# UpperMotor_v1_0_2.net
KiCad netlist of a schematic drawn in EasyEDA Pro
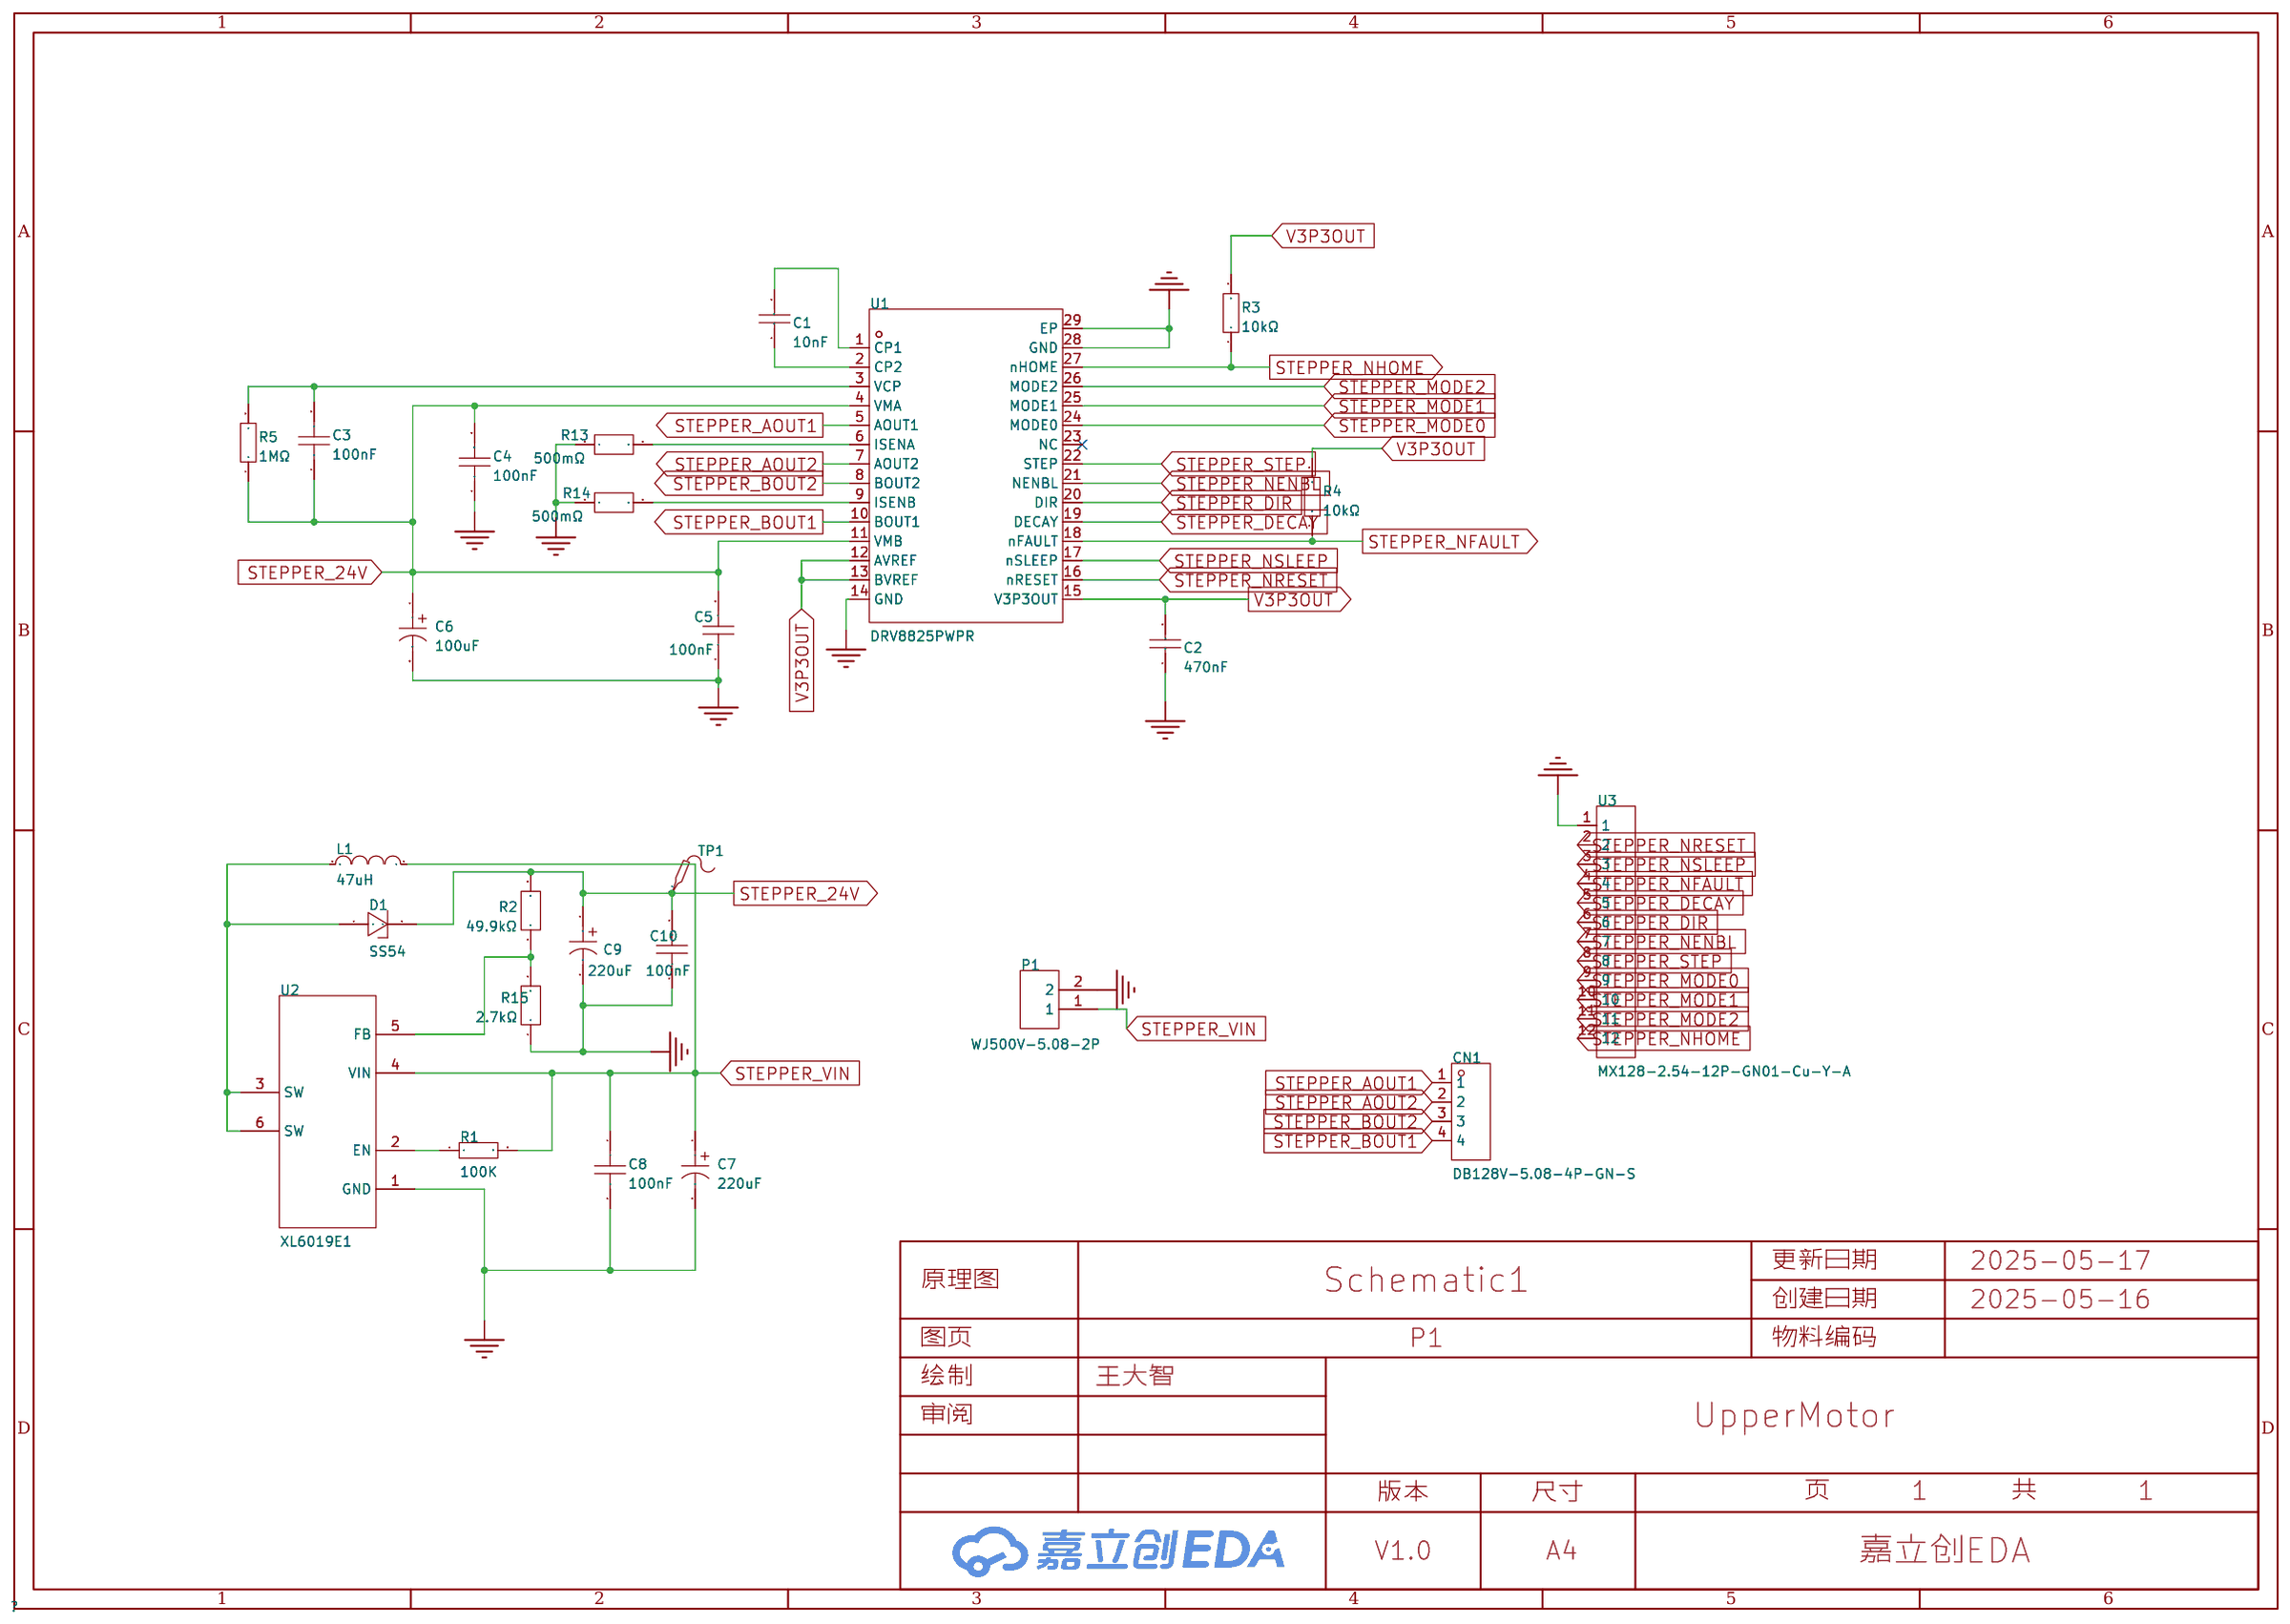
[diagram p0: schematic sheet]

(export (version "E")
  (design (tool "Eeschema 10.0.6"))
  (components
    (comp (ref "C1")
      (value "10nF")
      (footprint "easyedapro:C0603")
      (description "容值:10nF;精度:±10%;额定电压:50V;材质(温度系数):X7R;")
      (fields
        (field (name "Manufacturer Part") "CL10B103KB8NNNC")
        (field (name "Manufacturer") "SAMSUNG(三星)")
      )
      (libsource (lib "easyedapro") (part "CL10B103KB8NNNC"))
    )
    (comp (ref "C2")
      (value "470nF")
      (footprint "easyedapro:C0603")
      (description "容值:470nF;精度:±10%;额定电压:25V;材质(温度系数):X7R;")
      (fields
        (field (name "Manufacturer Part") "CL10B474KA8NNNC")
        (field (name "Manufacturer") "SAMSUNG(三星)")
      )
      (libsource (lib "easyedapro") (part "CL10B474KA8NNNC"))
    )
    (comp (ref "C3")
      (value "100nF")
      (footprint "easyedapro:C0603")
      (description "容值:100nF;精度:±10%;额定电压:50V;温度系数:X7R;")
      (fields
        (field (name "Manufacturer Part") "CGA0603X7R104K500JT")
        (field (name "Manufacturer") "HRE(芯声)")
      )
      (libsource (lib "easyedapro") (part "CGA0603X7R104K500JT"))
    )
    (comp (ref "C4")
      (value "100nF")
      (footprint "easyedapro:C0603")
      (description "容值:100nF;精度:±10%;额定电压:50V;温度系数:X7R;")
      (fields
        (field (name "Manufacturer Part") "CGA0603X7R104K500JT")
        (field (name "Manufacturer") "HRE(芯声)")
      )
      (libsource (lib "easyedapro") (part "CGA0603X7R104K500JT"))
    )
    (comp (ref "C5")
      (value "100nF")
      (footprint "easyedapro:C0603")
      (description "容值:100nF;精度:±10%;额定电压:50V;温度系数:X7R;")
      (fields
        (field (name "Manufacturer Part") "CGA0603X7R104K500JT")
        (field (name "Manufacturer") "HRE(芯声)")
      )
      (libsource (lib "easyedapro") (part "CGA0603X7R104K500JT"))
    )
    (comp (ref "C6")
      (value "100uF")
      (footprint "easyedapro:CAP-SMD_BD8.1-L8.3-W8.3-LS9.3-FD")
      (description "容值:100uF;精度:±20%;额定电压:50V;纹波电流:300mA@100kHz;等效串联电阻:600mΩ@100kHz;")
      (fields
        (field (name "Manufacturer Part") "GVE1H107M0810CNVC")
        (field (name "Manufacturer") "HRK(鸿瑞凯电子)")
      )
      (libsource (lib "easyedapro") (part "GVE1H107M0810CNVC"))
    )
    (comp (ref "C7")
      (value "220uF")
      (footprint "easyedapro:CAP-SMD_BD8.0-L8.3-W8.3-FD")
      (description "容值:220uF;精度:±20%;额定电压:35V;纹波电流:175mA@120Hz;")
      (fields
        (field (name "Manufacturer Part") "GVT1V227M0810CNVC")
        (field (name "Manufacturer") "HRK(鸿瑞凯电子)")
      )
      (libsource (lib "easyedapro") (part "GVT1V227M0810CNVC"))
    )
    (comp (ref "C8")
      (value "100nF")
      (footprint "easyedapro:C0603")
      (libsource (lib "easyedapro") (part "CapAcitance"))
    )
    (comp (ref "C9")
      (value "220uF")
      (footprint "easyedapro:CAP-SMD_BD8.0-L8.3-W8.3-FD")
      (description "容值:220uF;精度:±20%;额定电压:35V;纹波电流:175mA@120Hz;")
      (fields
        (field (name "Manufacturer Part") "GVT1V227M0810CNVC")
        (field (name "Manufacturer") "HRK(鸿瑞凯电子)")
      )
      (libsource (lib "easyedapro") (part "GVT1V227M0810CNVC"))
    )
    (comp (ref "C10")
      (value "100nF")
      (footprint "easyedapro:C0603")
      (libsource (lib "easyedapro") (part "CapAcitance"))
    )
    (comp (ref "CN1")
      (value "DB128V-5.08-4P-GN-S")
      (footprint "easyedapro:CONN-TH_4P-P5.08_DIBO_DB128V-5.08")
      (fields (field (name "Manufacturer") "DORABO(地博电气)"))
      (libsource (lib "easyedapro") (part "DB128V-5.08-4P-GN-S"))
    )
    (comp (ref "D1")
      (value "SS54")
      (footprint "easyedapro:SMA_L4.3-W2.6-LS5.0-FD")
      (description "二极管配置:独立式;正向压降(Vf):550mV@5.0A;直流反向耐压(Vr):40V;整流电流:5A;")
      (fields (field (name "Manufacturer") "宏迦橙"))
      (libsource (lib "easyedapro") (part "SS54_C7420369"))
    )
    (comp (ref "L1")
      (value "47uH")
      (footprint "easyedapro:IND-SMD_L11.5-W10.0_SMMS1040")
      (description "电感值:47uH;精度:±20%;额定电流:3A;饱和电流(Isat):4.5A;类型:一体成型电感;")
      (fields (field (name "Manufacturer Part") "SMMS1040-470M") (field (name "Manufacturer") "SXN(顺翔诺)"))
      (libsource (lib "easyedapro") (part "SMMS1040-470M"))
    )
    (comp (ref "P1")
      (value "WJ500V-5.08-2P")
      (footprint "easyedapro:CONN-TH_2P-P5.00_WJ500V-5.08-2P")
      (fields (field (name "Manufacturer") "KANGNEX(康奈克斯电气)"))
      (libsource (lib "easyedapro") (part "WJ500V-5.08-2P-14-00A"))
    )
    (comp (ref "R1") (value "100K") (footprint "easyedapro:R0603") (libsource (lib "easyedapro") (part "电阻")))
    (comp (ref "R2")
      (value "49.9kΩ")
      (footprint "easyedapro:R0603")
      (description "电阻类型:厚膜电阻;阻值:49.9kΩ;精度:±1%;功率:100mW;最大工作电压:75V;温度系数:±100ppm/°C;")
      (fields (field (name "Manufacturer Part") "FRC0603F4992TS") (field (name "Manufacturer") "FOJAN(富捷)"))
      (libsource (lib "easyedapro") (part "FRC0603F4992TS"))
    )
    (comp (ref "R3")
      (value "10kΩ")
      (footprint "easyedapro:R0603")
      (description "电阻类型:厚膜电阻;阻值:10kΩ;精度:±1%;功率:100mW;最大工作电压:75V;温度系数:±100ppm/°C;")
      (fields (field (name "Manufacturer Part") "RC0603FR-0710KL") (field (name "Manufacturer") "YAGEO(国巨)"))
      (libsource (lib "easyedapro") (part "RC0603FR-0710KL"))
    )
    (comp (ref "R4")
      (value "10kΩ")
      (footprint "easyedapro:R0603")
      (description "电阻类型:厚膜电阻;阻值:10kΩ;精度:±1%;功率:100mW;最大工作电压:75V;温度系数:±100ppm/°C;")
      (fields (field (name "Manufacturer Part") "RC0603FR-0710KL") (field (name "Manufacturer") "YAGEO(国巨)"))
      (libsource (lib "easyedapro") (part "RC0603FR-0710KL"))
    )
    (comp (ref "R5")
      (value "1MΩ")
      (footprint "easyedapro:R0603")
      (fields
        (field (name "Manufacturer Part") "0603WAF1004T5E")
        (field (name "Manufacturer") "UNI-ROYAL(厚声)")
      )
      (libsource (lib "easyedapro") (part "电阻"))
    )
    (comp (ref "R13")
      (value "500mΩ")
      (footprint "easyedapro:R0603")
      (description "电阻类型:厚膜电阻;阻值:500mΩ;精度:±5%;功率:100mW;最大工作电压:100V;温度系数:±300ppm/°C;")
      (fields (field (name "Manufacturer Part") "FRL0603JR500TS") (field (name "Manufacturer") "FOJAN(富捷)"))
      (libsource (lib "easyedapro") (part "FRL0603JR500TS"))
    )
    (comp (ref "R14")
      (value "500mΩ")
      (footprint "easyedapro:R0603")
      (description "电阻类型:厚膜电阻;阻值:500mΩ;精度:±5%;功率:100mW;最大工作电压:100V;温度系数:±300ppm/°C;")
      (fields (field (name "Manufacturer Part") "FRL0603JR500TS") (field (name "Manufacturer") "FOJAN(富捷)"))
      (libsource (lib "easyedapro") (part "FRL0603JR500TS"))
    )
    (comp (ref "R15")
      (value "2.7kΩ")
      (footprint "easyedapro:R0603")
      (description "电阻类型:厚膜电阻;阻值:2.7kΩ;精度:±1%;功率:100mW;工作电压:75V;温度系数:±100ppm/°C;")
      (fields (field (name "Manufacturer Part") "FRC0603F2701TS") (field (name "Manufacturer") "FOJAN(富捷)"))
      (libsource (lib "easyedapro") (part "FRC0603F2701TS"))
    )
    (comp (ref "TP1")
      (value "~")
      (footprint "easyedapro:Test-Point-0.5mm")
      (description "Test Point 测试点")
      (libsource (lib "easyedapro") (part "Test-Point"))
    )
    (comp (ref "U1")
      (value "DRV8825PWPR")
      (footprint "easyedapro:HTSSOP-28_L9.7-W4.4-P0.65-LS6.4-BL-EP")
      (description "DRV8825 具有电流调节功能和 1/32 微步进的 45V、2.5A 双极步进电机驱动器")
      (fields (field (name "Manufacturer") "TI(德州仪器)"))
      (libsource (lib "easyedapro") (part "DRV8825PWPR"))
    )
    (comp (ref "U2")
      (value "XL6019E1")
      (footprint "easyedapro:TO-263-5_L10.2-W9.9-P1.70-LS14.4-TL")
      (description "功能类型:升降压型;输出类型:可调;工作电压:5V~40V;输出电压:-;输出电流:5A;")
      (fields (field (name "Manufacturer") "XLSEMI(芯龙)"))
      (libsource (lib "easyedapro") (part "XL6019E1"))
    )
    (comp (ref "U3")
      (value "MX128-2.54-12P-GN01-Cu-Y-A")
      (footprint "easyedapro:CONN-TH_12P-P2.54_MX128-2.54-12P-GN01-CU-Y-A")
      (fields (field (name "Manufacturer") "MAX(迈旭)"))
      (libsource (lib "easyedapro") (part "MX128-2.54-12P-GN01-CU-Y-A"))
    )
  )
  (nets
    (net (code "1") (name "GND") (class "Default")
      (node (ref "C10") (pin "1") (pinfunction "1_1") (pintype "input"))
      (node (ref "C2") (pin "1") (pinfunction "1_1") (pintype "input"))
      (node (ref "C4") (pin "1") (pinfunction "1_1") (pintype "unspecified"))
      (node (ref "C5") (pin "1") (pinfunction "1_1") (pintype "unspecified"))
      (node (ref "C6") (pin "2") (pinfunction "2_2") (pintype "input"))
      (node (ref "C7") (pin "2") (pinfunction "2_2") (pintype "input"))
      (node (ref "C8") (pin "2") (pinfunction "2_2") (pintype "input"))
      (node (ref "C9") (pin "2") (pinfunction "2_2") (pintype "input"))
      (node (ref "P1") (pin "2") (pinfunction "2_2") (pintype "unspecified"))
      (node (ref "R13") (pin "1") (pinfunction "1_1") (pintype "unspecified"))
      (node (ref "R14") (pin "1") (pinfunction "1_1") (pintype "unspecified"))
      (node (ref "R15") (pin "1") (pinfunction "1_1") (pintype "unspecified"))
      (node (ref "U1") (pin "14") (pinfunction "GND_14") (pintype "unspecified"))
      (node (ref "U1") (pin "28") (pinfunction "GND_28") (pintype "unspecified"))
      (node (ref "U1") (pin "29") (pinfunction "EP_29") (pintype "unspecified"))
      (node (ref "U2") (pin "1") (pinfunction "GND_1") (pintype "unspecified"))
      (node (ref "U3") (pin "1") (pinfunction "1_1") (pintype "unspecified"))
    )
    (net (code "2") (name "Net-(D1-A)") (class "Default")
      (node (ref "D1") (pin "1") (pinfunction "A_1") (pintype "unspecified"))
      (node (ref "L1") (pin "1") (pinfunction "1_1") (pintype "unspecified"))
      (node (ref "U2") (pin "3") (pinfunction "SW_3") (pintype "unspecified"))
      (node (ref "U2") (pin "6") (pinfunction "SW_6") (pintype "unspecified"))
    )
    (net (code "3") (name "Net-(U1-CP1)") (class "Default")
      (node (ref "C1") (pin "2") (pinfunction "2_2") (pintype "input"))
      (node (ref "U1") (pin "1") (pinfunction "CP1_1") (pintype "unspecified"))
    )
    (net (code "4") (name "Net-(U1-CP2)") (class "Default")
      (node (ref "C1") (pin "1") (pinfunction "1_1") (pintype "input"))
      (node (ref "U1") (pin "2") (pinfunction "CP2_2") (pintype "unspecified"))
    )
    (net (code "5") (name "Net-(U1-ISENA)") (class "Default")
      (node (ref "R13") (pin "2") (pinfunction "2_2") (pintype "unspecified"))
      (node (ref "U1") (pin "6") (pinfunction "ISENA_6") (pintype "unspecified"))
    )
    (net (code "6") (name "Net-(U1-ISENB)") (class "Default")
      (node (ref "R14") (pin "2") (pinfunction "2_2") (pintype "unspecified"))
      (node (ref "U1") (pin "9") (pinfunction "ISENB_9") (pintype "unspecified"))
    )
    (net (code "7") (name "Net-(U1-VCP)") (class "Default")
      (node (ref "C3") (pin "2") (pinfunction "2_2") (pintype "unspecified"))
      (node (ref "R5") (pin "2") (pinfunction "2_2") (pintype "input"))
      (node (ref "U1") (pin "3") (pinfunction "VCP_3") (pintype "unspecified"))
    )
    (net (code "8") (name "Net-(U2-EN)") (class "Default")
      (node (ref "R1") (pin "1") (pinfunction "1_1") (pintype "input"))
      (node (ref "U2") (pin "2") (pinfunction "EN_2") (pintype "unspecified"))
    )
    (net (code "9") (name "Net-(U2-FB)") (class "Default")
      (node (ref "R15") (pin "2") (pinfunction "2_2") (pintype "unspecified"))
      (node (ref "R2") (pin "1") (pinfunction "1_1") (pintype "unspecified"))
      (node (ref "U2") (pin "5") (pinfunction "FB_5") (pintype "unspecified"))
    )
    (net (code "10") (name "STEPPER_24V") (class "Default")
      (node (ref "C10") (pin "2") (pinfunction "2_2") (pintype "input"))
      (node (ref "C3") (pin "1") (pinfunction "1_1") (pintype "unspecified"))
      (node (ref "C4") (pin "2") (pinfunction "2_2") (pintype "unspecified"))
      (node (ref "C5") (pin "2") (pinfunction "2_2") (pintype "unspecified"))
      (node (ref "C6") (pin "1") (pinfunction "1_1") (pintype "input"))
      (node (ref "C9") (pin "1") (pinfunction "1_1") (pintype "input"))
      (node (ref "D1") (pin "2") (pinfunction "K_2") (pintype "unspecified"))
      (node (ref "R2") (pin "2") (pinfunction "2_2") (pintype "unspecified"))
      (node (ref "R5") (pin "1") (pinfunction "1_1") (pintype "input"))
      (node (ref "TP1") (pin "1") (pinfunction "1_1") (pintype "input"))
      (node (ref "U1") (pin "11") (pinfunction "VMB_11") (pintype "unspecified"))
      (node (ref "U1") (pin "4") (pinfunction "VMA_4") (pintype "unspecified"))
    )
    (net (code "11") (name "STEPPER_AOUT1") (class "Default")
      (node (ref "CN1") (pin "1") (pinfunction "1_1") (pintype "unspecified"))
      (node (ref "U1") (pin "5") (pinfunction "AOUT1_5") (pintype "unspecified"))
    )
    (net (code "12") (name "STEPPER_AOUT2") (class "Default")
      (node (ref "CN1") (pin "2") (pinfunction "2_2") (pintype "unspecified"))
      (node (ref "U1") (pin "7") (pinfunction "AOUT2_7") (pintype "unspecified"))
    )
    (net (code "13") (name "STEPPER_BOUT1") (class "Default")
      (node (ref "CN1") (pin "4") (pinfunction "4_4") (pintype "unspecified"))
      (node (ref "U1") (pin "10") (pinfunction "BOUT1_10") (pintype "unspecified"))
    )
    (net (code "14") (name "STEPPER_BOUT2") (class "Default")
      (node (ref "CN1") (pin "3") (pinfunction "3_3") (pintype "unspecified"))
      (node (ref "U1") (pin "8") (pinfunction "BOUT2_8") (pintype "unspecified"))
    )
    (net (code "15") (name "STEPPER_DECAY") (class "Default")
      (node (ref "U1") (pin "19") (pinfunction "DECAY_19") (pintype "unspecified"))
      (node (ref "U3") (pin "5") (pinfunction "5_5") (pintype "unspecified"))
    )
    (net (code "16") (name "STEPPER_DIR") (class "Default")
      (node (ref "U1") (pin "20") (pinfunction "DIR_20") (pintype "unspecified"))
      (node (ref "U3") (pin "6") (pinfunction "6_6") (pintype "unspecified"))
    )
    (net (code "17") (name "STEPPER_MODE0") (class "Default")
      (node (ref "U1") (pin "24") (pinfunction "MODE0_24") (pintype "unspecified"))
      (node (ref "U3") (pin "9") (pinfunction "9_9") (pintype "unspecified"))
    )
    (net (code "18") (name "STEPPER_MODE1") (class "Default")
      (node (ref "U1") (pin "25") (pinfunction "MODE1_25") (pintype "unspecified"))
      (node (ref "U3") (pin "10") (pinfunction "10_10") (pintype "unspecified"))
    )
    (net (code "19") (name "STEPPER_MODE2") (class "Default")
      (node (ref "U1") (pin "26") (pinfunction "MODE2_26") (pintype "unspecified"))
      (node (ref "U3") (pin "11") (pinfunction "11_11") (pintype "unspecified"))
    )
    (net (code "20") (name "STEPPER_NENBL") (class "Default")
      (node (ref "U1") (pin "21") (pinfunction "NENBL_21") (pintype "unspecified"))
      (node (ref "U3") (pin "7") (pinfunction "7_7") (pintype "unspecified"))
    )
    (net (code "21") (name "STEPPER_NFAULT") (class "Default")
      (node (ref "R4") (pin "1") (pinfunction "1_1") (pintype "input"))
      (node (ref "U1") (pin "18") (pinfunction "nFAULT_18") (pintype "unspecified"))
      (node (ref "U3") (pin "4") (pinfunction "4_4") (pintype "unspecified"))
    )
    (net (code "22") (name "STEPPER_NHOME") (class "Default")
      (node (ref "R3") (pin "1") (pinfunction "1_1") (pintype "input"))
      (node (ref "U1") (pin "27") (pinfunction "nHOME_27") (pintype "unspecified"))
      (node (ref "U3") (pin "12") (pinfunction "12_12") (pintype "unspecified"))
    )
    (net (code "23") (name "STEPPER_NRESET") (class "Default")
      (node (ref "U1") (pin "16") (pinfunction "nRESET_16") (pintype "unspecified"))
      (node (ref "U3") (pin "2") (pinfunction "2_2") (pintype "unspecified"))
    )
    (net (code "24") (name "STEPPER_NSLEEP") (class "Default")
      (node (ref "U1") (pin "17") (pinfunction "nSLEEP_17") (pintype "unspecified"))
      (node (ref "U3") (pin "3") (pinfunction "3_3") (pintype "unspecified"))
    )
    (net (code "25") (name "STEPPER_STEP") (class "Default")
      (node (ref "U1") (pin "22") (pinfunction "STEP_22") (pintype "unspecified"))
      (node (ref "U3") (pin "8") (pinfunction "8_8") (pintype "unspecified"))
    )
    (net (code "26") (name "STEPPER_VIN") (class "Default")
      (node (ref "C7") (pin "1") (pinfunction "1_1") (pintype "input"))
      (node (ref "C8") (pin "1") (pinfunction "1_1") (pintype "input"))
      (node (ref "L1") (pin "2") (pinfunction "2_2") (pintype "unspecified"))
      (node (ref "P1") (pin "1") (pinfunction "1_1") (pintype "unspecified"))
      (node (ref "R1") (pin "2") (pinfunction "2_2") (pintype "input"))
      (node (ref "U2") (pin "4") (pinfunction "VIN_4") (pintype "unspecified"))
    )
    (net (code "27") (name "V3P3OUT") (class "Default")
      (node (ref "C2") (pin "2") (pinfunction "2_2") (pintype "input"))
      (node (ref "R3") (pin "2") (pinfunction "2_2") (pintype "input"))
      (node (ref "R4") (pin "2") (pinfunction "2_2") (pintype "input"))
      (node (ref "U1") (pin "12") (pinfunction "AVREF_12") (pintype "unspecified"))
      (node (ref "U1") (pin "13") (pinfunction "BVREF_13") (pintype "unspecified"))
      (node (ref "U1") (pin "15") (pinfunction "V3P3OUT_15") (pintype "unspecified"))
    )
    (net (code "28") (name "unconnected-(U1-NC-Pad23)") (class "Default")
      (node (ref "U1") (pin "23") (pinfunction "NC_23") (pintype "unspecified+no_connect"))
    )
  )
)
